# Sheet1-driver.net
KiCad netlist of a schematic drawn in Altium Designer
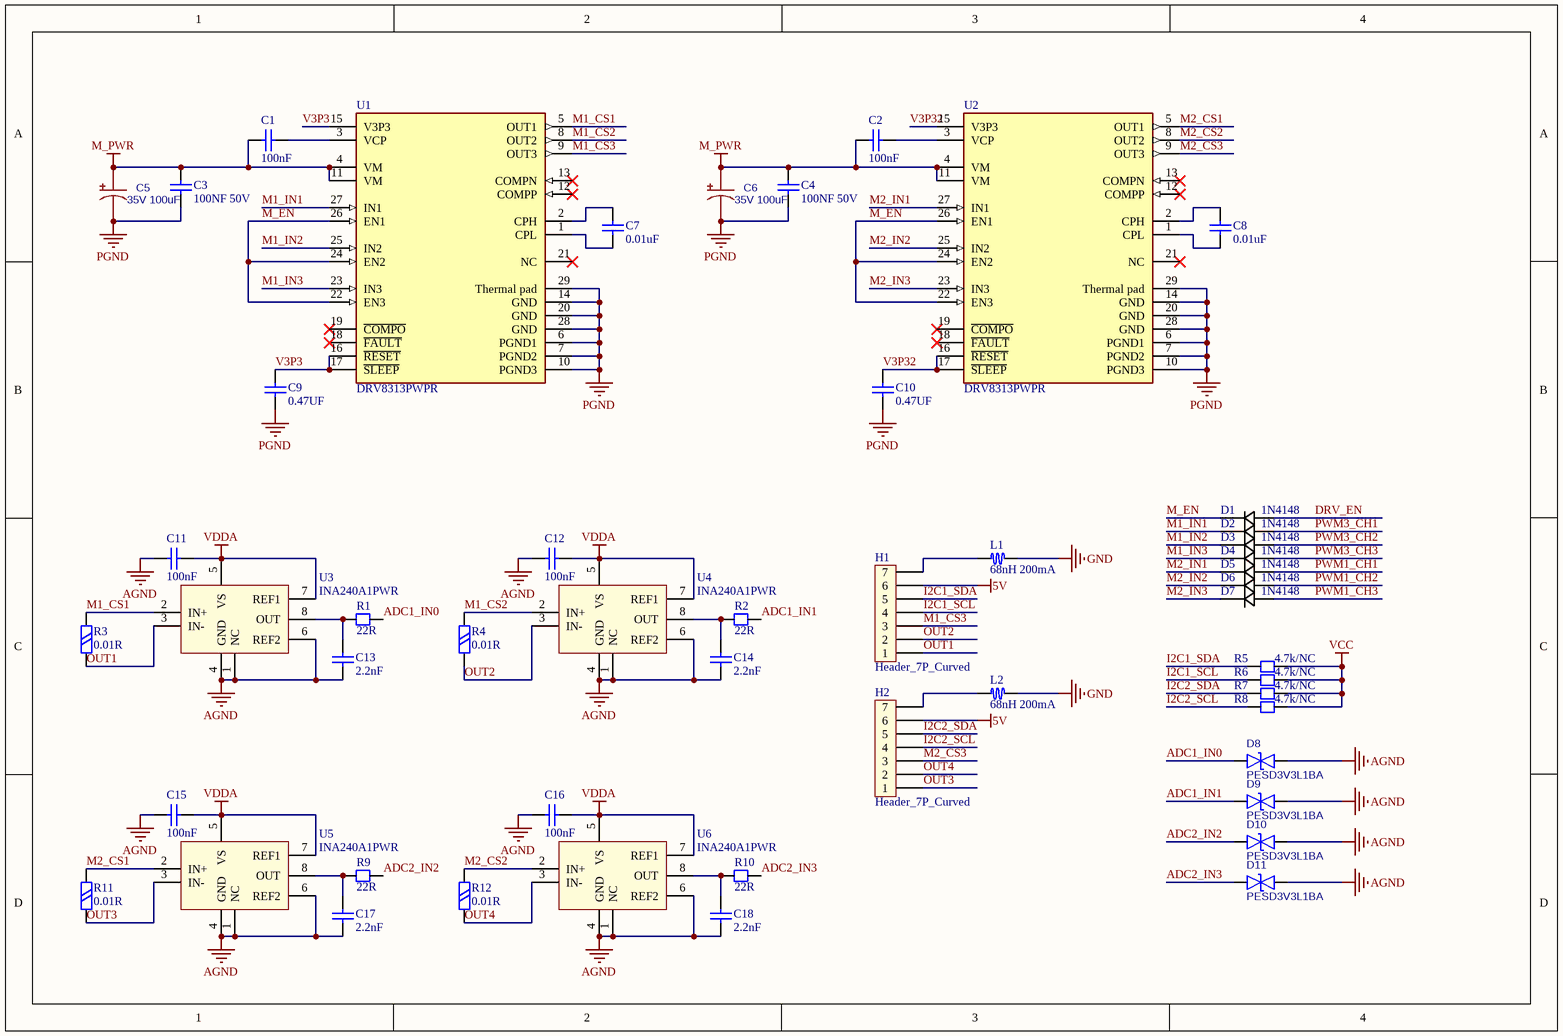
[diagram p0: Sheet1-driver.SchDoc]

(export (version "E")
  (design (tool "Eeschema 10.0.6"))
  (components
    (comp (ref "C1")
      (value "100nF")
      (footprint "CC1608-0603")
      (description "0603封装的电容")
      (fields (field (name "PUBLISHER") "Altium Limited"))
      (libsource (lib "base") (part "Cap Chip 0603"))
    )
    (comp (ref "C2")
      (value "100nF")
      (footprint "CC1608-0603")
      (description "0603封装的电容")
      (fields (field (name "PUBLISHER") "Altium Limited"))
      (libsource (lib "base") (part "Cap Chip 0603"))
    )
    (comp (ref "C3")
      (value "100NF 50V")
      (footprint "CC1608-0603")
      (description "0603封装的电容")
      (fields (field (name "PUBLISHER") "Altium Limited"))
      (libsource (lib "base") (part "Cap Chip 0603"))
    )
    (comp (ref "C4")
      (value "100NF 50V")
      (footprint "CC1608-0603")
      (description "0603封装的电容")
      (fields (field (name "PUBLISHER") "Altium Limited"))
      (libsource (lib "base") (part "Cap Chip 0603"))
    )
    (comp (ref "C5")
      (value "35V 100uF")
      (footprint "CAP-SMD_D6.3")
      (description "铝点解电容")
      (fields
        (field (name "BOM_SUPPLIER PART") "C413527")
        (field (name "BOM_MANUFACTURER PART") "EEEFP1C681AP")
        (field (name "CONTRIBUTOR") "LCSC")
      )
      (libsource (lib "base") (part "Cap ECAP SMD"))
    )
    (comp (ref "C6")
      (value "35V 100uF")
      (footprint "CAP-SMD_D6.3")
      (description "铝点解电容")
      (fields
        (field (name "BOM_SUPPLIER PART") "C413527")
        (field (name "BOM_MANUFACTURER PART") "EEEFP1C681AP")
        (field (name "CONTRIBUTOR") "LCSC")
      )
      (libsource (lib "base") (part "Cap ECAP SMD"))
    )
    (comp (ref "C7")
      (value "0.01uF")
      (footprint "CC1608-0603")
      (description "0603封装的电容")
      (fields (field (name "PUBLISHER") "Altium Limited"))
      (libsource (lib "base") (part "Cap Chip 0603"))
    )
    (comp (ref "C8")
      (value "0.01uF")
      (footprint "CC1608-0603")
      (description "0603封装的电容")
      (fields (field (name "PUBLISHER") "Altium Limited"))
      (libsource (lib "base") (part "Cap Chip 0603"))
    )
    (comp (ref "C9")
      (value "0.47UF")
      (footprint "CC1608-0603")
      (description "0603封装的电容")
      (fields (field (name "PUBLISHER") "Altium Limited"))
      (libsource (lib "base") (part "Cap Chip 0603"))
    )
    (comp (ref "C10")
      (value "0.47UF")
      (footprint "CC1608-0603")
      (description "0603封装的电容")
      (fields (field (name "PUBLISHER") "Altium Limited"))
      (libsource (lib "base") (part "Cap Chip 0603"))
    )
    (comp (ref "C11")
      (value "100nF")
      (footprint "CC1608-0603")
      (description "0603封装的电容")
      (fields (field (name "PUBLISHER") "Altium Limited"))
      (libsource (lib "base") (part "Cap Chip 0603"))
    )
    (comp (ref "C12")
      (value "100nF")
      (footprint "CC1608-0603")
      (description "0603封装的电容")
      (fields (field (name "PUBLISHER") "Altium Limited"))
      (libsource (lib "base") (part "Cap Chip 0603"))
    )
    (comp (ref "C13")
      (value "2.2nF")
      (footprint "CC1608-0603")
      (description "0603封装的电容")
      (fields (field (name "PUBLISHER") "Altium Limited"))
      (libsource (lib "base") (part "Cap Chip 0603"))
    )
    (comp (ref "C14")
      (value "2.2nF")
      (footprint "CC1608-0603")
      (description "0603封装的电容")
      (fields (field (name "PUBLISHER") "Altium Limited"))
      (libsource (lib "base") (part "Cap Chip 0603"))
    )
    (comp (ref "C15")
      (value "100nF")
      (footprint "CC1608-0603")
      (description "0603封装的电容")
      (fields (field (name "PUBLISHER") "Altium Limited"))
      (libsource (lib "base") (part "Cap Chip 0603"))
    )
    (comp (ref "C16")
      (value "100nF")
      (footprint "CC1608-0603")
      (description "0603封装的电容")
      (fields (field (name "PUBLISHER") "Altium Limited"))
      (libsource (lib "base") (part "Cap Chip 0603"))
    )
    (comp (ref "C17")
      (value "2.2nF")
      (footprint "CC1608-0603")
      (description "0603封装的电容")
      (fields (field (name "PUBLISHER") "Altium Limited"))
      (libsource (lib "base") (part "Cap Chip 0603"))
    )
    (comp (ref "C18")
      (value "2.2nF")
      (footprint "CC1608-0603")
      (description "0603封装的电容")
      (fields (field (name "PUBLISHER") "Altium Limited"))
      (libsource (lib "base") (part "Cap Chip 0603"))
    )
    (comp (ref "D1")
      (value "1N4148")
      (footprint "SOD-323")
      (description "1N5819 SOD-323封装 小体积SS14 印S4 肖特基二极管")
      (libsource (lib "transistor") (part "1N4148"))
    )
    (comp (ref "D2")
      (value "1N4148")
      (footprint "SOD-323")
      (description "1N5819 SOD-323封装 小体积SS14 印S4 肖特基二极管")
      (libsource (lib "transistor") (part "1N4148"))
    )
    (comp (ref "D3")
      (value "1N4148")
      (footprint "SOD-323")
      (description "1N5819 SOD-323封装 小体积SS14 印S4 肖特基二极管")
      (libsource (lib "transistor") (part "1N4148"))
    )
    (comp (ref "D4")
      (value "1N4148")
      (footprint "SOD-323")
      (description "1N5819 SOD-323封装 小体积SS14 印S4 肖特基二极管")
      (libsource (lib "transistor") (part "1N4148"))
    )
    (comp (ref "D5")
      (value "1N4148")
      (footprint "SOD-323")
      (description "1N5819 SOD-323封装 小体积SS14 印S4 肖特基二极管")
      (libsource (lib "transistor") (part "1N4148"))
    )
    (comp (ref "D6")
      (value "1N4148")
      (footprint "SOD-323")
      (description "1N5819 SOD-323封装 小体积SS14 印S4 肖特基二极管")
      (libsource (lib "transistor") (part "1N4148"))
    )
    (comp (ref "D7")
      (value "1N4148")
      (footprint "SOD-323")
      (description "1N5819 SOD-323封装 小体积SS14 印S4 肖特基二极管")
      (libsource (lib "transistor") (part "1N4148"))
    )
    (comp (ref "D8")
      (value "PESD3V3L1BA")
      (footprint "SOD-323")
      (description "SOD-323 3.3V 双向ESD防静电二极管保护芯片")
      (fields (field (name "MANUFACTURER") "MDD") (field (name "MANUFACTURER PART") "SMAJ6.5CA"))
      (libsource (lib "transistor") (part "PESD3V3L1BA"))
    )
    (comp (ref "D9")
      (value "PESD3V3L1BA")
      (footprint "SOD-323")
      (description "SOD-323 3.3V 双向ESD防静电二极管保护芯片")
      (fields (field (name "MANUFACTURER") "MDD") (field (name "MANUFACTURER PART") "SMAJ6.5CA"))
      (libsource (lib "transistor") (part "PESD3V3L1BA"))
    )
    (comp (ref "D10")
      (value "PESD3V3L1BA")
      (footprint "SOD-323")
      (description "SOD-323 3.3V 双向ESD防静电二极管保护芯片")
      (fields (field (name "MANUFACTURER") "MDD") (field (name "MANUFACTURER PART") "SMAJ6.5CA"))
      (libsource (lib "transistor") (part "PESD3V3L1BA"))
    )
    (comp (ref "D11")
      (value "PESD3V3L1BA")
      (footprint "SOD-323")
      (description "SOD-323 3.3V 双向ESD防静电二极管保护芯片")
      (fields (field (name "MANUFACTURER") "MDD") (field (name "MANUFACTURER PART") "SMAJ6.5CA"))
      (libsource (lib "transistor") (part "PESD3V3L1BA"))
    )
    (comp (ref "H1")
      (value "Header_7P_Curved")
      (footprint "Header_2_54_7PW")
      (description "弯的6P排针")
      (libsource (lib "base") (part "Header_7P_Curved"))
    )
    (comp (ref "H2")
      (value "Header_7P_Curved")
      (footprint "Header_2_54_7PW")
      (description "弯的6P排针")
      (libsource (lib "base") (part "Header_7P_Curved"))
    )
    (comp (ref "L1")
      (value "68nH 200mA")
      (footprint "Inductor-0603")
      (description "贴片电感 0603封装")
      (libsource (lib "base") (part "Inductor-0603"))
    )
    (comp (ref "L2")
      (value "68nH 200mA")
      (footprint "Inductor-0603")
      (description "贴片电感 0603封装")
      (libsource (lib "base") (part "Inductor-0603"))
    )
    (comp (ref "R1")
      (value "22R")
      (footprint "CR1608-0603")
      (description "0603封装电阻")
      (fields (field (name "PUBLISHER") "Altium Limited"))
      (libsource (lib "") (part "Resistor Chip 0603_1"))
    )
    (comp (ref "R2")
      (value "22R")
      (footprint "CR1608-0603")
      (description "0603封装电阻")
      (fields (field (name "PUBLISHER") "Altium Limited"))
      (libsource (lib "") (part "Resistor Chip 0603_1"))
    )
    (comp (ref "R3")
      (value "0.01R")
      (footprint "CR3216-1206")
      (description "1206封装电阻")
      (fields (field (name "PUBLISHER") "Altium Limited"))
      (libsource (lib "base") (part "Resistor Chip 1206"))
    )
    (comp (ref "R4")
      (value "0.01R")
      (footprint "CR3216-1206")
      (description "1206封装电阻")
      (fields (field (name "PUBLISHER") "Altium Limited"))
      (libsource (lib "base") (part "Resistor Chip 1206"))
    )
    (comp (ref "R5")
      (value "4.7k/NC")
      (footprint "CR1608-0603")
      (description "0603封装电阻")
      (fields (field (name "PUBLISHER") "Altium Limited"))
      (libsource (lib "base") (part "Resistor Chip 0603"))
    )
    (comp (ref "R6")
      (value "4.7k/NC")
      (footprint "CR1608-0603")
      (description "0603封装电阻")
      (fields (field (name "PUBLISHER") "Altium Limited"))
      (libsource (lib "base") (part "Resistor Chip 0603"))
    )
    (comp (ref "R7")
      (value "4.7k/NC")
      (footprint "CR1608-0603")
      (description "0603封装电阻")
      (fields (field (name "PUBLISHER") "Altium Limited"))
      (libsource (lib "base") (part "Resistor Chip 0603"))
    )
    (comp (ref "R8")
      (value "4.7k/NC")
      (footprint "CR1608-0603")
      (description "0603封装电阻")
      (fields (field (name "PUBLISHER") "Altium Limited"))
      (libsource (lib "base") (part "Resistor Chip 0603"))
    )
    (comp (ref "R9")
      (value "22R")
      (footprint "CR1608-0603")
      (description "0603封装电阻")
      (fields (field (name "PUBLISHER") "Altium Limited"))
      (libsource (lib "") (part "Resistor Chip 0603_1"))
    )
    (comp (ref "R10")
      (value "22R")
      (footprint "CR1608-0603")
      (description "0603封装电阻")
      (fields (field (name "PUBLISHER") "Altium Limited"))
      (libsource (lib "") (part "Resistor Chip 0603_1"))
    )
    (comp (ref "R11")
      (value "0.01R")
      (footprint "CR3216-1206")
      (description "1206封装电阻")
      (fields (field (name "PUBLISHER") "Altium Limited"))
      (libsource (lib "base") (part "Resistor Chip 1206"))
    )
    (comp (ref "R12")
      (value "0.01R")
      (footprint "CR3216-1206")
      (description "1206封装电阻")
      (fields (field (name "PUBLISHER") "Altium Limited"))
      (libsource (lib "base") (part "Resistor Chip 1206"))
    )
    (comp (ref "U1")
      (value "DRV8313PWPR")
      (footprint "HTSSOP-28")
      (description "独立控制的半 H 桥驱动器,主要用于驱动一个三项无刷电机IC MOTOR DRIVER 8V-60V 28HTSSOP")
      (libsource (lib "PB-Chip") (part "DRV8313"))
    )
    (comp (ref "U2")
      (value "DRV8313PWPR")
      (footprint "HTSSOP-28")
      (description "独立控制的半 H 桥驱动器,主要用于驱动一个三项无刷电机IC MOTOR DRIVER 8V-60V 28HTSSOP")
      (libsource (lib "PB-Chip") (part "DRV8313"))
    )
    (comp (ref "U3")
      (value "INA240A1PWR")
      (footprint "TSSOP-8")
      (description "超精密电流检测放大器")
      (libsource (lib "power-chip") (part "INA240A1PWR"))
    )
    (comp (ref "U4")
      (value "INA240A1PWR")
      (footprint "TSSOP-8")
      (description "超精密电流检测放大器")
      (libsource (lib "power-chip") (part "INA240A1PWR"))
    )
    (comp (ref "U5")
      (value "INA240A1PWR")
      (footprint "TSSOP-8")
      (description "超精密电流检测放大器")
      (libsource (lib "power-chip") (part "INA240A1PWR"))
    )
    (comp (ref "U6")
      (value "INA240A1PWR")
      (footprint "TSSOP-8")
      (description "超精密电流检测放大器")
      (libsource (lib "power-chip") (part "INA240A1PWR"))
    )
  )
  (nets
    (net (code "1") (name "/ADC1_IN0") (class "Default")
      (node (ref "D8") (pin "1") (pinfunction "1_1") (pintype "passive"))
      (node (ref "R1") (pin "1") (pinfunction "1_1") (pintype "passive"))
    )
    (net (code "2") (name "/ADC1_IN1") (class "Default")
      (node (ref "D9") (pin "1") (pinfunction "1_1") (pintype "passive"))
      (node (ref "R2") (pin "1") (pinfunction "1_1") (pintype "passive"))
    )
    (net (code "3") (name "/ADC2_IN2") (class "Default")
      (node (ref "D10") (pin "1") (pinfunction "1_1") (pintype "passive"))
      (node (ref "R9") (pin "1") (pinfunction "1_1") (pintype "passive"))
    )
    (net (code "4") (name "/ADC2_IN3") (class "Default")
      (node (ref "D11") (pin "1") (pinfunction "1_1") (pintype "passive"))
      (node (ref "R10") (pin "1") (pinfunction "1_1") (pintype "passive"))
    )
    (net (code "5") (name "/DRV_EN") (class "Default")
      (node (ref "D1") (pin "2") (pinfunction "2_2") (pintype "passive"))
    )
    (net (code "6") (name "/I2C1_SCL") (class "Default")
      (node (ref "H1") (pin "4") (pinfunction "4_4") (pintype "passive"))
      (node (ref "R6") (pin "1") (pinfunction "1_1") (pintype "passive"))
    )
    (net (code "7") (name "/I2C1_SDA") (class "Default")
      (node (ref "H1") (pin "5") (pinfunction "5_5") (pintype "passive"))
      (node (ref "R5") (pin "1") (pinfunction "1_1") (pintype "passive"))
    )
    (net (code "8") (name "/I2C2_SCL") (class "Default")
      (node (ref "H2") (pin "4") (pinfunction "4_4") (pintype "passive"))
      (node (ref "R8") (pin "1") (pinfunction "1_1") (pintype "passive"))
    )
    (net (code "9") (name "/I2C2_SDA") (class "Default")
      (node (ref "H2") (pin "5") (pinfunction "5_5") (pintype "passive"))
      (node (ref "R7") (pin "1") (pinfunction "1_1") (pintype "passive"))
    )
    (net (code "10") (name "/M1_CS1") (class "Default")
      (node (ref "R3") (pin "2") (pinfunction "2_2") (pintype "passive"))
      (node (ref "U1") (pin "5") (pinfunction "OUT1_5") (pintype "output"))
      (node (ref "U3") (pin "2") (pinfunction "IN+_2") (pintype "passive"))
    )
    (net (code "11") (name "/M1_CS2") (class "Default")
      (node (ref "R4") (pin "2") (pinfunction "2_2") (pintype "passive"))
      (node (ref "U1") (pin "8") (pinfunction "OUT2_8") (pintype "output"))
      (node (ref "U4") (pin "2") (pinfunction "IN+_2") (pintype "passive"))
    )
    (net (code "12") (name "/M1_CS3") (class "Default")
      (node (ref "H1") (pin "3") (pinfunction "3_3") (pintype "passive"))
      (node (ref "U1") (pin "9") (pinfunction "OUT3_9") (pintype "output"))
    )
    (net (code "13") (name "/M1_IN1") (class "Default")
      (node (ref "D2") (pin "1") (pinfunction "1_1") (pintype "passive"))
      (node (ref "U1") (pin "27") (pinfunction "IN1_27") (pintype "input"))
    )
    (net (code "14") (name "/M1_IN2") (class "Default")
      (node (ref "D3") (pin "1") (pinfunction "1_1") (pintype "passive"))
      (node (ref "U1") (pin "25") (pinfunction "IN2_25") (pintype "input"))
    )
    (net (code "15") (name "/M1_IN3") (class "Default")
      (node (ref "D4") (pin "1") (pinfunction "1_1") (pintype "passive"))
      (node (ref "U1") (pin "23") (pinfunction "IN3_23") (pintype "input"))
    )
    (net (code "16") (name "/M2_CS1") (class "Default")
      (node (ref "R11") (pin "2") (pinfunction "2_2") (pintype "passive"))
      (node (ref "U2") (pin "5") (pinfunction "OUT1_5") (pintype "output"))
      (node (ref "U5") (pin "2") (pinfunction "IN+_2") (pintype "passive"))
    )
    (net (code "17") (name "/M2_CS2") (class "Default")
      (node (ref "R12") (pin "2") (pinfunction "2_2") (pintype "passive"))
      (node (ref "U2") (pin "8") (pinfunction "OUT2_8") (pintype "output"))
      (node (ref "U6") (pin "2") (pinfunction "IN+_2") (pintype "passive"))
    )
    (net (code "18") (name "/M2_CS3") (class "Default")
      (node (ref "H2") (pin "3") (pinfunction "3_3") (pintype "passive"))
      (node (ref "U2") (pin "9") (pinfunction "OUT3_9") (pintype "output"))
    )
    (net (code "19") (name "/M2_IN1") (class "Default")
      (node (ref "D5") (pin "1") (pinfunction "1_1") (pintype "passive"))
      (node (ref "U2") (pin "27") (pinfunction "IN1_27") (pintype "input"))
    )
    (net (code "20") (name "/M2_IN2") (class "Default")
      (node (ref "D6") (pin "1") (pinfunction "1_1") (pintype "passive"))
      (node (ref "U2") (pin "25") (pinfunction "IN2_25") (pintype "input"))
    )
    (net (code "21") (name "/M2_IN3") (class "Default")
      (node (ref "D7") (pin "1") (pinfunction "1_1") (pintype "passive"))
      (node (ref "U2") (pin "23") (pinfunction "IN3_23") (pintype "input"))
    )
    (net (code "22") (name "/M_EN") (class "Default")
      (node (ref "D1") (pin "1") (pinfunction "1_1") (pintype "passive"))
      (node (ref "U1") (pin "22") (pinfunction "EN3_22") (pintype "input"))
      (node (ref "U1") (pin "24") (pinfunction "EN2_24") (pintype "input"))
      (node (ref "U1") (pin "26") (pinfunction "EN1_26") (pintype "input"))
      (node (ref "U2") (pin "22") (pinfunction "EN3_22") (pintype "input"))
      (node (ref "U2") (pin "24") (pinfunction "EN2_24") (pintype "input"))
      (node (ref "U2") (pin "26") (pinfunction "EN1_26") (pintype "input"))
    )
    (net (code "23") (name "/OUT1") (class "Default")
      (node (ref "H1") (pin "1") (pinfunction "1_1") (pintype "passive"))
      (node (ref "R3") (pin "1") (pinfunction "1_1") (pintype "passive"))
      (node (ref "U3") (pin "3") (pinfunction "IN-_3") (pintype "passive"))
    )
    (net (code "24") (name "/OUT2") (class "Default")
      (node (ref "H1") (pin "2") (pinfunction "2_2") (pintype "passive"))
      (node (ref "R4") (pin "1") (pinfunction "1_1") (pintype "passive"))
      (node (ref "U4") (pin "3") (pinfunction "IN-_3") (pintype "passive"))
    )
    (net (code "25") (name "/OUT3") (class "Default")
      (node (ref "H2") (pin "1") (pinfunction "1_1") (pintype "passive"))
      (node (ref "R11") (pin "1") (pinfunction "1_1") (pintype "passive"))
      (node (ref "U5") (pin "3") (pinfunction "IN-_3") (pintype "passive"))
    )
    (net (code "26") (name "/OUT4") (class "Default")
      (node (ref "H2") (pin "2") (pinfunction "2_2") (pintype "passive"))
      (node (ref "R12") (pin "1") (pinfunction "1_1") (pintype "passive"))
      (node (ref "U6") (pin "3") (pinfunction "IN-_3") (pintype "passive"))
    )
    (net (code "27") (name "/PWM1_CH1") (class "Default")
      (node (ref "D5") (pin "2") (pinfunction "2_2") (pintype "passive"))
    )
    (net (code "28") (name "/PWM1_CH2") (class "Default")
      (node (ref "D6") (pin "2") (pinfunction "2_2") (pintype "passive"))
    )
    (net (code "29") (name "/PWM1_CH3") (class "Default")
      (node (ref "D7") (pin "2") (pinfunction "2_2") (pintype "passive"))
    )
    (net (code "30") (name "/PWM3_CH1") (class "Default")
      (node (ref "D2") (pin "2") (pinfunction "2_2") (pintype "passive"))
    )
    (net (code "31") (name "/PWM3_CH2") (class "Default")
      (node (ref "D3") (pin "2") (pinfunction "2_2") (pintype "passive"))
    )
    (net (code "32") (name "/PWM3_CH3") (class "Default")
      (node (ref "D4") (pin "2") (pinfunction "2_2") (pintype "passive"))
    )
    (net (code "33") (name "/V3P3") (class "Default")
      (node (ref "C9") (pin "1") (pinfunction "1_1") (pintype "passive"))
      (node (ref "U1") (pin "15") (pinfunction "V3P3_15") (pintype "power_in"))
      (node (ref "U1") (pin "16") (pinfunction "~{RESET}_16") (pintype "passive"))
      (node (ref "U1") (pin "17") (pinfunction "~{SLEEP}_17") (pintype "passive"))
    )
    (net (code "34") (name "/V3P32") (class "Default")
      (node (ref "C10") (pin "1") (pinfunction "1_1") (pintype "passive"))
      (node (ref "U2") (pin "15") (pinfunction "V3P3_15") (pintype "power_in"))
      (node (ref "U2") (pin "16") (pinfunction "~{RESET}_16") (pintype "passive"))
      (node (ref "U2") (pin "17") (pinfunction "~{SLEEP}_17") (pintype "passive"))
    )
    (net (code "35") (name "5V") (class "Default")
      (node (ref "H1") (pin "6") (pinfunction "6_6") (pintype "passive"))
      (node (ref "H2") (pin "6") (pinfunction "6_6") (pintype "passive"))
    )
    (net (code "36") (name "AGND") (class "Default")
      (node (ref "C11") (pin "2") (pinfunction "2_2") (pintype "passive"))
      (node (ref "C12") (pin "2") (pinfunction "2_2") (pintype "passive"))
      (node (ref "C13") (pin "1") (pinfunction "1_1") (pintype "passive"))
      (node (ref "C14") (pin "1") (pinfunction "1_1") (pintype "passive"))
      (node (ref "C15") (pin "2") (pinfunction "2_2") (pintype "passive"))
      (node (ref "C16") (pin "2") (pinfunction "2_2") (pintype "passive"))
      (node (ref "C17") (pin "1") (pinfunction "1_1") (pintype "passive"))
      (node (ref "C18") (pin "1") (pinfunction "1_1") (pintype "passive"))
      (node (ref "D10") (pin "2") (pinfunction "2_2") (pintype "passive"))
      (node (ref "D11") (pin "2") (pinfunction "2_2") (pintype "passive"))
      (node (ref "D8") (pin "2") (pinfunction "2_2") (pintype "passive"))
      (node (ref "D9") (pin "2") (pinfunction "2_2") (pintype "passive"))
      (node (ref "U3") (pin "1") (pinfunction "NC_1") (pintype "passive"))
      (node (ref "U3") (pin "4") (pinfunction "GND_4") (pintype "passive"))
      (node (ref "U3") (pin "6") (pinfunction "REF2_6") (pintype "passive"))
      (node (ref "U4") (pin "1") (pinfunction "NC_1") (pintype "passive"))
      (node (ref "U4") (pin "4") (pinfunction "GND_4") (pintype "passive"))
      (node (ref "U4") (pin "6") (pinfunction "REF2_6") (pintype "passive"))
      (node (ref "U5") (pin "1") (pinfunction "NC_1") (pintype "passive"))
      (node (ref "U5") (pin "4") (pinfunction "GND_4") (pintype "passive"))
      (node (ref "U5") (pin "6") (pinfunction "REF2_6") (pintype "passive"))
      (node (ref "U6") (pin "1") (pinfunction "NC_1") (pintype "passive"))
      (node (ref "U6") (pin "4") (pinfunction "GND_4") (pintype "passive"))
      (node (ref "U6") (pin "6") (pinfunction "REF2_6") (pintype "passive"))
    )
    (net (code "37") (name "GND") (class "Default")
      (node (ref "L1") (pin "2") (pinfunction "2_2") (pintype "passive"))
      (node (ref "L2") (pin "2") (pinfunction "2_2") (pintype "passive"))
    )
    (net (code "38") (name "M_PWR") (class "Default")
      (node (ref "C1") (pin "2") (pinfunction "2_2") (pintype "passive"))
      (node (ref "C2") (pin "2") (pinfunction "2_2") (pintype "passive"))
      (node (ref "C3") (pin "1") (pinfunction "1_1") (pintype "passive"))
      (node (ref "C4") (pin "1") (pinfunction "1_1") (pintype "passive"))
      (node (ref "C5") (pin "1") (pinfunction "1_1") (pintype "passive"))
      (node (ref "C6") (pin "1") (pinfunction "1_1") (pintype "passive"))
      (node (ref "U1") (pin "11") (pinfunction "VM_11") (pintype "power_in"))
      (node (ref "U1") (pin "4") (pinfunction "VM_4") (pintype "power_in"))
      (node (ref "U2") (pin "11") (pinfunction "VM_11") (pintype "power_in"))
      (node (ref "U2") (pin "4") (pinfunction "VM_4") (pintype "power_in"))
    )
    (net (code "39") (name "Net-(H1-Pad7)") (class "Default")
      (node (ref "H1") (pin "7") (pinfunction "7_7") (pintype "passive"))
      (node (ref "L1") (pin "1") (pinfunction "1_1") (pintype "passive"))
    )
    (net (code "40") (name "Net-(H2-Pad7)") (class "Default")
      (node (ref "H2") (pin "7") (pinfunction "7_7") (pintype "passive"))
      (node (ref "L2") (pin "1") (pinfunction "1_1") (pintype "passive"))
    )
    (net (code "41") (name "Net-(U1-CPH)") (class "Default")
      (node (ref "C7") (pin "1") (pinfunction "1_1") (pintype "passive"))
      (node (ref "U1") (pin "2") (pinfunction "CPH_2") (pintype "power_in"))
    )
    (net (code "42") (name "Net-(U1-CPL)") (class "Default")
      (node (ref "C7") (pin "2") (pinfunction "2_2") (pintype "passive"))
      (node (ref "U1") (pin "1") (pinfunction "CPL_1") (pintype "power_in"))
    )
    (net (code "43") (name "Net-(U1-VCP)") (class "Default")
      (node (ref "C1") (pin "1") (pinfunction "1_1") (pintype "passive"))
      (node (ref "U1") (pin "3") (pinfunction "VCP_3") (pintype "power_in"))
    )
    (net (code "44") (name "Net-(U2-CPH)") (class "Default")
      (node (ref "C8") (pin "1") (pinfunction "1_1") (pintype "passive"))
      (node (ref "U2") (pin "2") (pinfunction "CPH_2") (pintype "power_in"))
    )
    (net (code "45") (name "Net-(U2-CPL)") (class "Default")
      (node (ref "C8") (pin "2") (pinfunction "2_2") (pintype "passive"))
      (node (ref "U2") (pin "1") (pinfunction "CPL_1") (pintype "power_in"))
    )
    (net (code "46") (name "Net-(U2-VCP)") (class "Default")
      (node (ref "C2") (pin "1") (pinfunction "1_1") (pintype "passive"))
      (node (ref "U2") (pin "3") (pinfunction "VCP_3") (pintype "power_in"))
    )
    (net (code "47") (name "Net-(U3-OUT)") (class "Default")
      (node (ref "C13") (pin "2") (pinfunction "2_2") (pintype "passive"))
      (node (ref "R1") (pin "2") (pinfunction "2_2") (pintype "passive"))
      (node (ref "U3") (pin "8") (pinfunction "OUT_8") (pintype "passive"))
    )
    (net (code "48") (name "Net-(U4-OUT)") (class "Default")
      (node (ref "C14") (pin "2") (pinfunction "2_2") (pintype "passive"))
      (node (ref "R2") (pin "2") (pinfunction "2_2") (pintype "passive"))
      (node (ref "U4") (pin "8") (pinfunction "OUT_8") (pintype "passive"))
    )
    (net (code "49") (name "Net-(U5-OUT)") (class "Default")
      (node (ref "C17") (pin "2") (pinfunction "2_2") (pintype "passive"))
      (node (ref "R9") (pin "2") (pinfunction "2_2") (pintype "passive"))
      (node (ref "U5") (pin "8") (pinfunction "OUT_8") (pintype "passive"))
    )
    (net (code "50") (name "Net-(U6-OUT)") (class "Default")
      (node (ref "C18") (pin "2") (pinfunction "2_2") (pintype "passive"))
      (node (ref "R10") (pin "2") (pinfunction "2_2") (pintype "passive"))
      (node (ref "U6") (pin "8") (pinfunction "OUT_8") (pintype "passive"))
    )
    (net (code "51") (name "PGND") (class "Default")
      (node (ref "C10") (pin "2") (pinfunction "2_2") (pintype "passive"))
      (node (ref "C3") (pin "2") (pinfunction "2_2") (pintype "passive"))
      (node (ref "C4") (pin "2") (pinfunction "2_2") (pintype "passive"))
      (node (ref "C5") (pin "2") (pinfunction "2_2") (pintype "passive"))
      (node (ref "C6") (pin "2") (pinfunction "2_2") (pintype "passive"))
      (node (ref "C9") (pin "2") (pinfunction "2_2") (pintype "passive"))
      (node (ref "U1") (pin "10") (pinfunction "PGND3_10") (pintype "power_in"))
      (node (ref "U1") (pin "14") (pinfunction "GND_14") (pintype "power_in"))
      (node (ref "U1") (pin "20") (pinfunction "GND_20") (pintype "power_in"))
      (node (ref "U1") (pin "28") (pinfunction "GND_28") (pintype "power_in"))
      (node (ref "U1") (pin "29") (pinfunction "Thermal_pad_29") (pintype "power_in"))
      (node (ref "U1") (pin "6") (pinfunction "PGND1_6") (pintype "power_in"))
      (node (ref "U1") (pin "7") (pinfunction "PGND2_7") (pintype "power_in"))
      (node (ref "U2") (pin "10") (pinfunction "PGND3_10") (pintype "power_in"))
      (node (ref "U2") (pin "14") (pinfunction "GND_14") (pintype "power_in"))
      (node (ref "U2") (pin "20") (pinfunction "GND_20") (pintype "power_in"))
      (node (ref "U2") (pin "28") (pinfunction "GND_28") (pintype "power_in"))
      (node (ref "U2") (pin "29") (pinfunction "Thermal_pad_29") (pintype "power_in"))
      (node (ref "U2") (pin "6") (pinfunction "PGND1_6") (pintype "power_in"))
      (node (ref "U2") (pin "7") (pinfunction "PGND2_7") (pintype "power_in"))
    )
    (net (code "52") (name "VCC") (class "Default")
      (node (ref "R5") (pin "2") (pinfunction "2_2") (pintype "passive"))
      (node (ref "R6") (pin "2") (pinfunction "2_2") (pintype "passive"))
      (node (ref "R7") (pin "2") (pinfunction "2_2") (pintype "passive"))
      (node (ref "R8") (pin "2") (pinfunction "2_2") (pintype "passive"))
    )
    (net (code "53") (name "VDDA") (class "Default")
      (node (ref "C11") (pin "1") (pinfunction "1_1") (pintype "passive"))
      (node (ref "C12") (pin "1") (pinfunction "1_1") (pintype "passive"))
      (node (ref "C15") (pin "1") (pinfunction "1_1") (pintype "passive"))
      (node (ref "C16") (pin "1") (pinfunction "1_1") (pintype "passive"))
      (node (ref "U3") (pin "5") (pinfunction "VS_5") (pintype "passive"))
      (node (ref "U3") (pin "7") (pinfunction "REF1_7") (pintype "passive"))
      (node (ref "U4") (pin "5") (pinfunction "VS_5") (pintype "passive"))
      (node (ref "U4") (pin "7") (pinfunction "REF1_7") (pintype "passive"))
      (node (ref "U5") (pin "5") (pinfunction "VS_5") (pintype "passive"))
      (node (ref "U5") (pin "7") (pinfunction "REF1_7") (pintype "passive"))
      (node (ref "U6") (pin "5") (pinfunction "VS_5") (pintype "passive"))
      (node (ref "U6") (pin "7") (pinfunction "REF1_7") (pintype "passive"))
    )
    (net (code "54") (name "unconnected-(U1-COMPN-Pad13)") (class "Default")
      (node (ref "U1") (pin "13") (pinfunction "COMPN_13") (pintype "input+no_connect"))
    )
    (net (code "55") (name "unconnected-(U1-COMPP-Pad12)") (class "Default")
      (node (ref "U1") (pin "12") (pinfunction "COMPP_12") (pintype "input+no_connect"))
    )
    (net (code "56") (name "unconnected-(U1-NC-Pad21)") (class "Default")
      (node (ref "U1") (pin "21") (pinfunction "NC_21") (pintype "passive+no_connect"))
    )
    (net (code "57") (name "unconnected-(U1-~{COMPO}-Pad19)") (class "Default")
      (node (ref "U1") (pin "19") (pinfunction "~{COMPO}_19") (pintype "open_collector+no_connect"))
    )
    (net (code "58") (name "unconnected-(U1-~{FAULT}-Pad18)") (class "Default")
      (node (ref "U1") (pin "18") (pinfunction "~{FAULT}_18") (pintype "open_collector+no_connect"))
    )
    (net (code "59") (name "unconnected-(U2-COMPN-Pad13)") (class "Default")
      (node (ref "U2") (pin "13") (pinfunction "COMPN_13") (pintype "input+no_connect"))
    )
    (net (code "60") (name "unconnected-(U2-COMPP-Pad12)") (class "Default")
      (node (ref "U2") (pin "12") (pinfunction "COMPP_12") (pintype "input+no_connect"))
    )
    (net (code "61") (name "unconnected-(U2-NC-Pad21)") (class "Default")
      (node (ref "U2") (pin "21") (pinfunction "NC_21") (pintype "passive+no_connect"))
    )
    (net (code "62") (name "unconnected-(U2-~{COMPO}-Pad19)") (class "Default")
      (node (ref "U2") (pin "19") (pinfunction "~{COMPO}_19") (pintype "open_collector+no_connect"))
    )
    (net (code "63") (name "unconnected-(U2-~{FAULT}-Pad18)") (class "Default")
      (node (ref "U2") (pin "18") (pinfunction "~{FAULT}_18") (pintype "open_collector+no_connect"))
    )
  )
)
